# C_v4.net
KiCad netlist of a schematic drawn in EasyEDA Pro
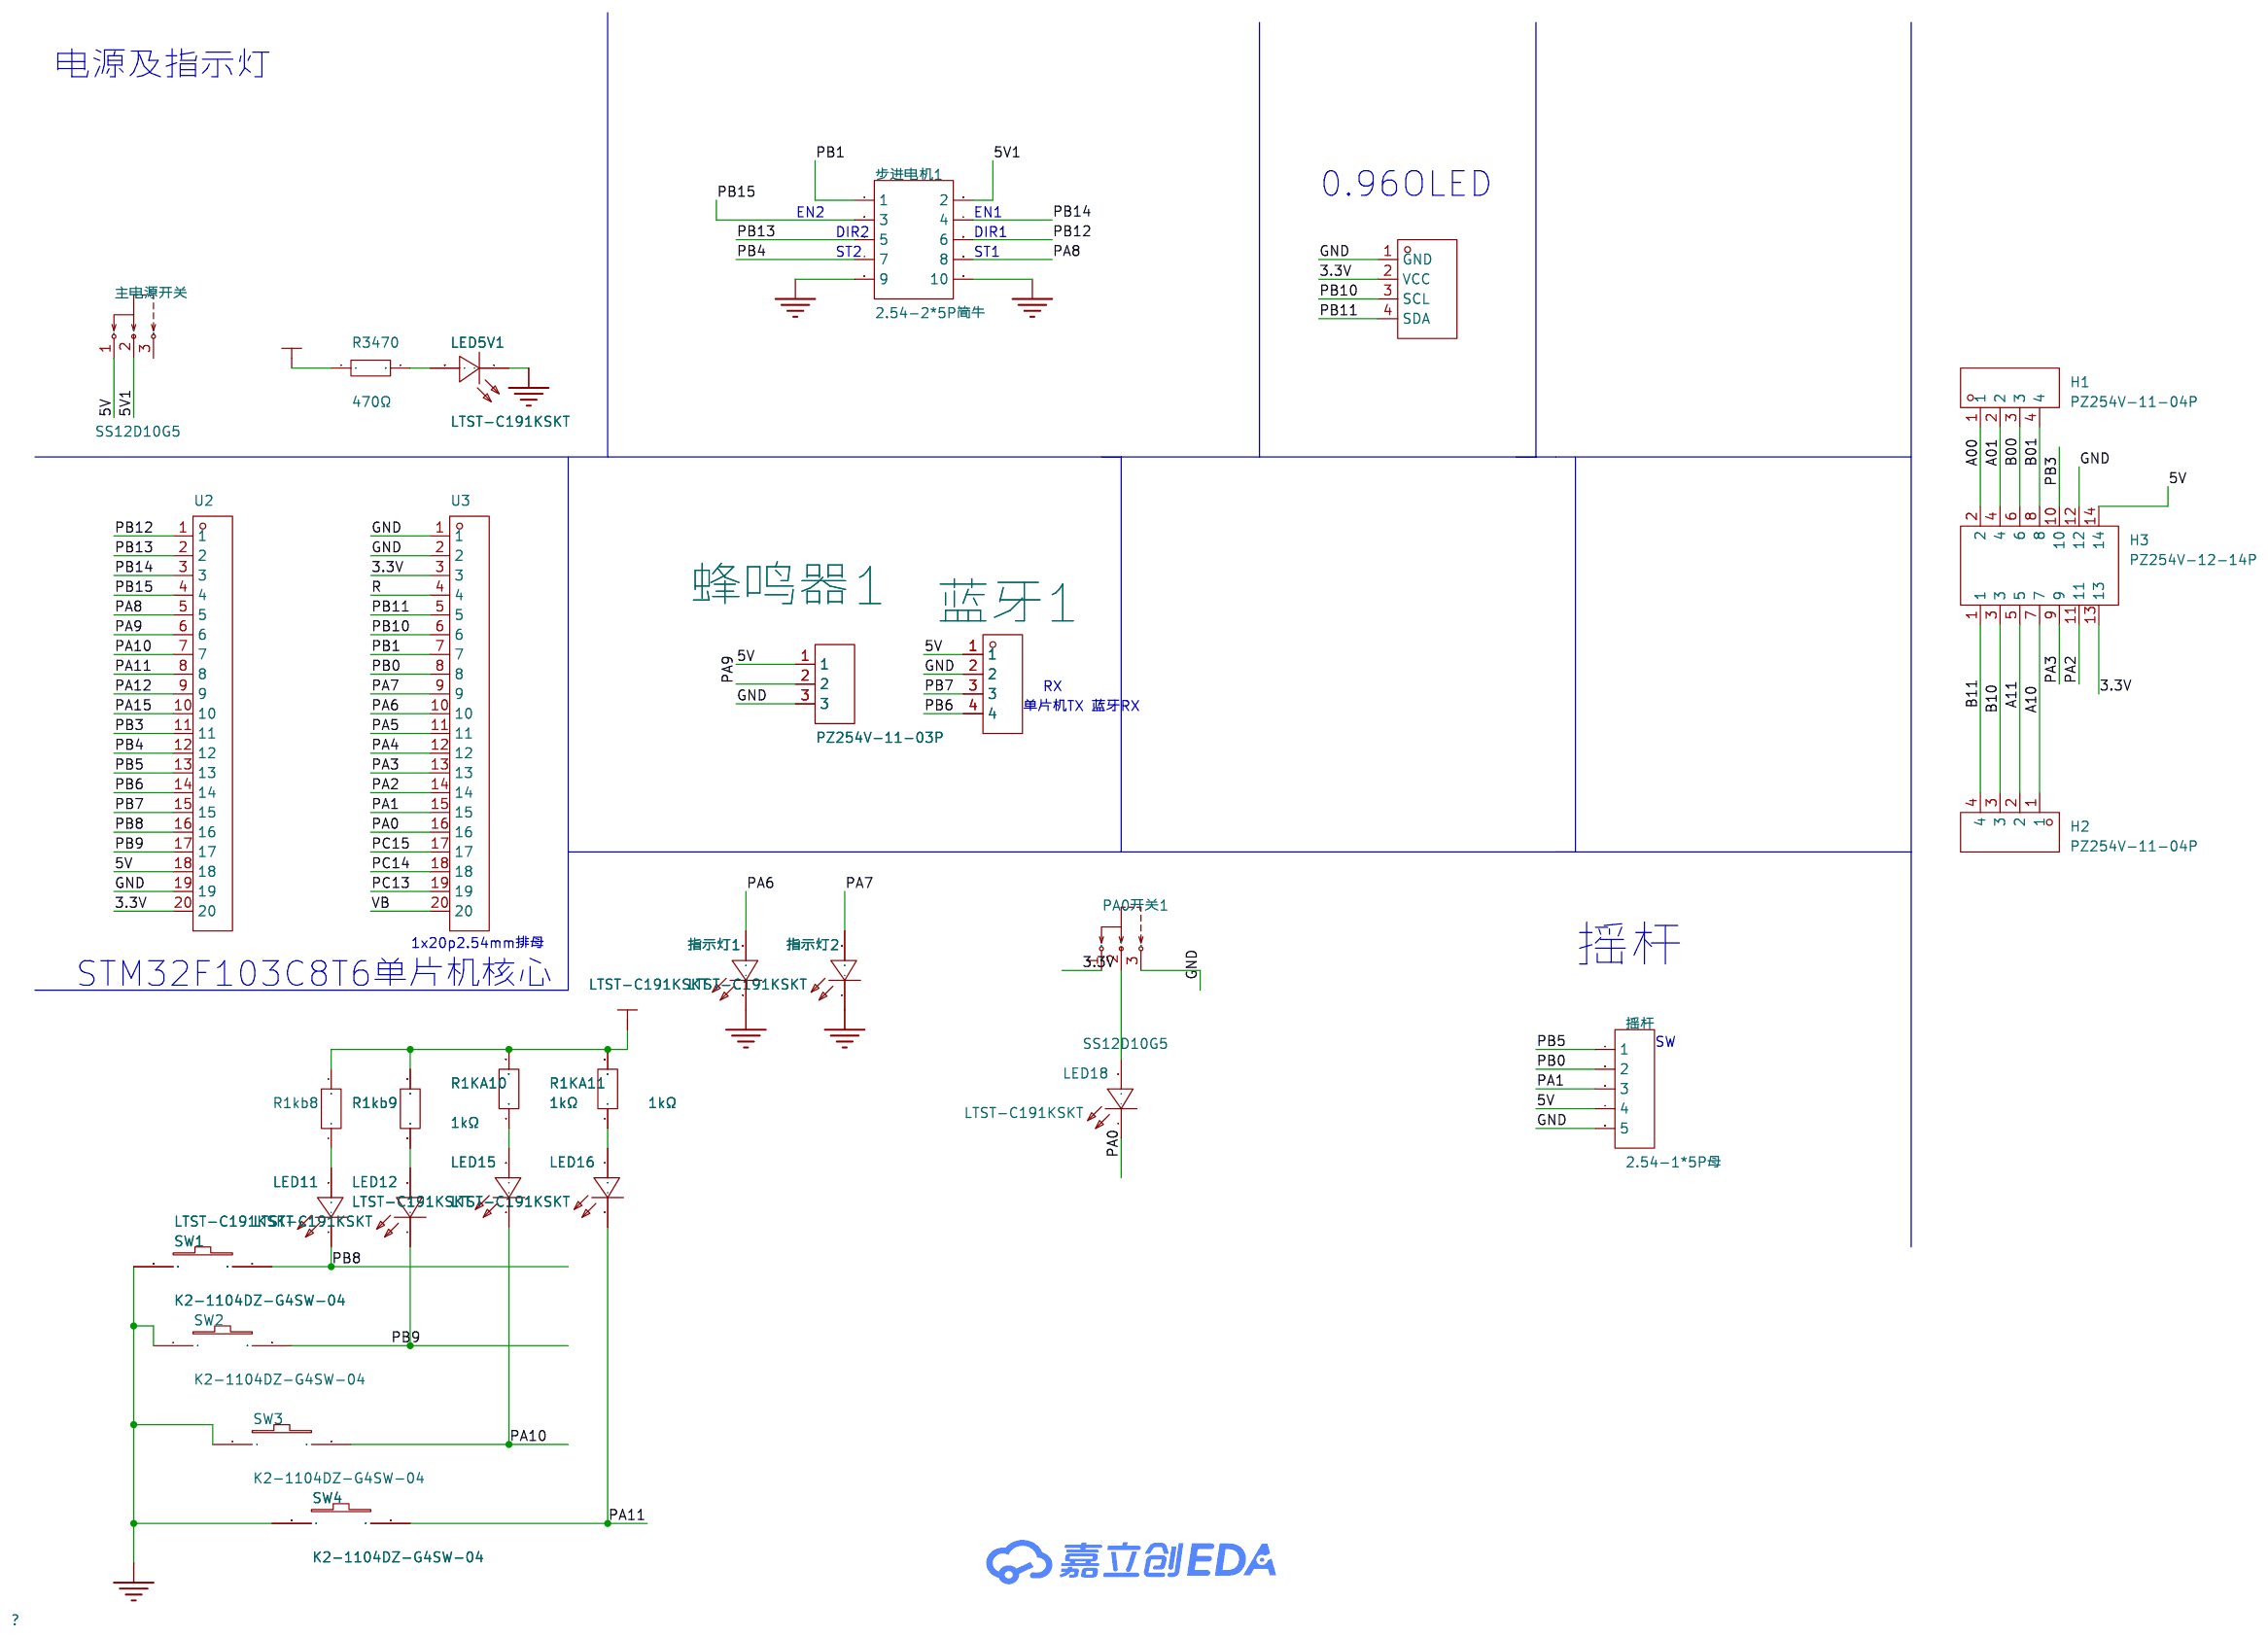
[diagram p0: schematic sheet]

(export (version "E")
  (design (tool "Eeschema 10.0.6"))
  (components
    (comp (ref "H1")
      (value "PZ254V-11-04P")
      (footprint "easyedapro:HDR-TH_4P-P2.54-V-M")
      (fields (field (name "Manufacturer") "XFCN(兴飞)"))
      (libsource (lib "easyedapro") (part "PZ254V-11-04P_C2691448"))
    )
    (comp (ref "H2")
      (value "PZ254V-11-04P")
      (footprint "easyedapro:HDR-TH_4P-P2.54-V-M")
      (fields (field (name "Manufacturer") "XFCN(兴飞)"))
      (libsource (lib "easyedapro") (part "PZ254V-11-04P_C2691448"))
    )
    (comp (ref "H3")
      (value "PZ254V-12-14P")
      (footprint "easyedapro:HDR-TH_14P-P2.54-V-M-R2-C7-S2.54")
      (fields (field (name "Manufacturer") "XFCN(兴飞)"))
      (libsource (lib "easyedapro") (part "PZ254V-12-14P"))
    )
    (comp (ref "LED5V1")
      (value "LTST-C191KSKT")
      (footprint "easyedapro:LED0603-RD-YELLOW")
      (fields (field (name "Manufacturer") "LITEON(光宝)"))
      (libsource (lib "easyedapro") (part "LTST-C191KSKT"))
    )
    (comp (ref "LED11")
      (value "LTST-C191KSKT")
      (footprint "easyedapro:LED0603-RD-YELLOW")
      (fields (field (name "Manufacturer") "LITEON(光宝)"))
      (libsource (lib "easyedapro") (part "LTST-C191KSKT"))
    )
    (comp (ref "LED12")
      (value "LTST-C191KSKT")
      (footprint "easyedapro:LED0603-RD-YELLOW")
      (fields (field (name "Manufacturer") "LITEON(光宝)"))
      (libsource (lib "easyedapro") (part "LTST-C191KSKT"))
    )
    (comp (ref "LED15")
      (value "LTST-C191KSKT")
      (footprint "easyedapro:LED0603-RD-YELLOW")
      (fields (field (name "Manufacturer") "LITEON(光宝)"))
      (libsource (lib "easyedapro") (part "LTST-C191KSKT"))
    )
    (comp (ref "LED16")
      (value "LTST-C191KSKT")
      (footprint "easyedapro:LED0603-RD-YELLOW")
      (fields (field (name "Manufacturer") "LITEON(光宝)"))
      (libsource (lib "easyedapro") (part "LTST-C191KSKT"))
    )
    (comp (ref "LED18")
      (value "LTST-C191KSKT")
      (footprint "easyedapro:LED0603-RD-YELLOW")
      (fields (field (name "Manufacturer") "LITEON(光宝)"))
      (libsource (lib "easyedapro") (part "LTST-C191KSKT"))
    )
    (comp (ref "OLED1")
      (value "HS96L03W2C03")
      (footprint "easyedapro:OLED-TH_L27.8-W27.2-P2.54_C9900033791")
      (description "主控芯片:SSD1315;接口类型:I2C;尺寸(inch):0.96;像素分辨率:128x64;")
      (fields (field (name "Manufacturer") "HS(汉昇)"))
      (libsource (lib "easyedapro") (part "HS96L03W2C03"))
    )
    (comp (ref "PA0开关1")
      (value "SS12D10G5")
      (footprint "easyedapro:SW-TH_SHOU-HAN_SS12D10G4")
      (description "电路结构:单刀双掷;安装方式:直插;额定电流(DC):2A;额定电压(DC):125V;机械寿命:3千次;")
      (fields (field (name "Manufacturer") "SHOU HAN(首韩)"))
      (libsource (lib "easyedapro") (part "SS12D10G5"))
    )
    (comp (ref "R1KA10")
      (value "1kΩ")
      (footprint "easyedapro:R0603")
      (description "电阻类型:厚膜电阻;阻值:1kΩ;精度:±1%;功率:100mW;最大工作电压:75V;")
      (fields (field (name "Manufacturer Part") "FCR0603F1K") (field (name "Manufacturer") "VO(翔胜)"))
      (libsource (lib "easyedapro") (part "FCR0603F1K"))
    )
    (comp (ref "R1KA11")
      (value "1kΩ")
      (footprint "easyedapro:R0603")
      (description "电阻类型:厚膜电阻;阻值:1kΩ;精度:±1%;功率:100mW;最大工作电压:75V;")
      (fields (field (name "Manufacturer Part") "FCR0603F1K") (field (name "Manufacturer") "VO(翔胜)"))
      (libsource (lib "easyedapro") (part "FCR0603F1K"))
    )
    (comp (ref "R1kb8")
      (value "1kΩ")
      (footprint "easyedapro:R0603")
      (description "电阻类型:厚膜电阻;阻值:1kΩ;精度:±1%;功率:100mW;最大工作电压:75V;")
      (fields (field (name "Manufacturer Part") "FCR0603F1K") (field (name "Manufacturer") "VO(翔胜)"))
      (libsource (lib "easyedapro") (part "FCR0603F1K"))
    )
    (comp (ref "R1kb9")
      (value "1kΩ")
      (footprint "easyedapro:R0603")
      (description "电阻类型:厚膜电阻;阻值:1kΩ;精度:±1%;功率:100mW;最大工作电压:75V;")
      (fields (field (name "Manufacturer Part") "FCR0603F1K") (field (name "Manufacturer") "VO(翔胜)"))
      (libsource (lib "easyedapro") (part "FCR0603F1K"))
    )
    (comp (ref "R3470")
      (value "470Ω")
      (footprint "easyedapro:R0603")
      (description "电阻类型:厚膜电阻;阻值:470Ω;精度:±1%;功率:100mW;最大工作电压:75V;温度系数:±100ppm/°C;")
      (fields
        (field (name "Manufacturer Part") "0603WAF4700T5E")
        (field (name "Manufacturer") "UNI-ROYAL(厚声)")
      )
      (libsource (lib "easyedapro") (part "0603WAF4700T5E"))
    )
    (comp (ref "SW1")
      (value "K2-1104DZ-G4SW-04")
      (footprint "easyedapro:KEY-TH_2P-L6.0-W6.0-P5.00")
      (description "作用力:250gf;安装方式:直插;开关长度:6mm;开关宽度:6mm;开关高度:7mm;触点电流:50mA;额定电压(DC):12V;绝缘电阻:100MΩ;机械寿命:10万次;")
      (fields (field (name "Manufacturer") "韩国韩荣"))
      (libsource (lib "easyedapro") (part "K2-1104DZ-G4SW-04"))
    )
    (comp (ref "SW2")
      (value "K2-1104DZ-G4SW-04")
      (footprint "easyedapro:KEY-TH_2P-L6.0-W6.0-P5.00")
      (description "作用力:250gf;安装方式:直插;开关长度:6mm;开关宽度:6mm;开关高度:7mm;触点电流:50mA;额定电压(DC):12V;绝缘电阻:100MΩ;机械寿命:10万次;")
      (fields (field (name "Manufacturer") "韩国韩荣"))
      (libsource (lib "easyedapro") (part "K2-1104DZ-G4SW-04"))
    )
    (comp (ref "SW3")
      (value "K2-1104DZ-G4SW-04")
      (footprint "easyedapro:KEY-TH_2P-L6.0-W6.0-P5.00")
      (description "作用力:250gf;安装方式:直插;开关长度:6mm;开关宽度:6mm;开关高度:7mm;触点电流:50mA;额定电压(DC):12V;绝缘电阻:100MΩ;机械寿命:10万次;")
      (fields (field (name "Manufacturer") "韩国韩荣"))
      (libsource (lib "easyedapro") (part "K2-1104DZ-G4SW-04"))
    )
    (comp (ref "SW4")
      (value "K2-1104DZ-G4SW-04")
      (footprint "easyedapro:KEY-TH_2P-L6.0-W6.0-P5.00")
      (description "作用力:250gf;安装方式:直插;开关长度:6mm;开关宽度:6mm;开关高度:7mm;触点电流:50mA;额定电压(DC):12V;绝缘电阻:100MΩ;机械寿命:10万次;")
      (fields (field (name "Manufacturer") "韩国韩荣"))
      (libsource (lib "easyedapro") (part "K2-1104DZ-G4SW-04"))
    )
    (comp (ref "U2")
      (value "KH-2FH-1X20P-H4.3")
      (footprint "easyedapro:HDR-TH_20P-P2.00-V-F-A")
      (fields (field (name "Manufacturer") "kinghelm(金航标)"))
      (libsource (lib "easyedapro") (part "KH-2FH-1X20P-H4.3"))
    )
    (comp (ref "U3")
      (value "KH-2FH-1X20P-H4.3")
      (footprint "easyedapro:HDR-TH_20P-P2.00-V-F-A")
      (fields (field (name "Manufacturer") "kinghelm(金航标)"))
      (libsource (lib "easyedapro") (part "KH-2FH-1X20P-H4.3"))
    )
    (comp (ref "主电源开关")
      (value "SS12D10G5")
      (footprint "easyedapro:SW-TH_SHOU-HAN_SS12D10G4")
      (description "电路结构:单刀双掷;安装方式:直插;额定电流(DC):2A;额定电压(DC):125V;机械寿命:3千次;")
      (fields (field (name "Manufacturer") "SHOU HAN(首韩)"))
      (libsource (lib "easyedapro") (part "SS12D10G5"))
    )
    (comp (ref "指示灯1")
      (value "LTST-C191KSKT")
      (footprint "easyedapro:LED0603-RD-YELLOW")
      (fields (field (name "Manufacturer") "LITEON(光宝)"))
      (libsource (lib "easyedapro") (part "LTST-C191KSKT"))
    )
    (comp (ref "指示灯2")
      (value "LTST-C191KSKT")
      (footprint "easyedapro:LED0603-RD-YELLOW")
      (fields (field (name "Manufacturer") "LITEON(光宝)"))
      (libsource (lib "easyedapro") (part "LTST-C191KSKT"))
    )
    (comp (ref "摇杆")
      (value "2.54-1*5P母")
      (footprint "easyedapro:HDR-TH_5P-P2.54-V-F")
      (description "插孔结构:1x5P;间距:2.54mm;行距:-;安装类型:直插;排数:单排;总孔位数:5P;塑高:-;触头材质:-;触头镀层:-;")
      (fields (field (name "Manufacturer") "BOOMELE(博穆精密)"))
      (libsource (lib "easyedapro") (part "Header-Female-2.54_1x5"))
    )
    (comp (ref "步进电机1")
      (value "2.54-2*5P简牛")
      (footprint "easyedapro:IDC-TH_10P-P2.54_C5665")
      (description "连接器类型:简牛座;间距:2.54mm;结构:2x5P;封装形式:直插;行距:2.54mm;排数:2;每排PIN数:5;触头材质:-;触头镀层:-;")
      (fields (field (name "Manufacturer") "BOOMELE(博穆精密)"))
      (libsource (lib "easyedapro") (part "HDR-IDC-2.54-2X5P"))
    )
    (comp (ref "蓝牙1")
      (value "2.54-1*4P母")
      (footprint "easyedapro:HDR-TH_4P-P2.54-V-F")
      (fields (field (name "Manufacturer") "BOOMELE(博穆精密)"))
      (libsource (lib "easyedapro") (part "2.54-1*4P母"))
    )
    (comp (ref "蜂鸣器1")
      (value "PZ254V-11-03P")
      (footprint "easyedapro:HDR-TH_3P-P2.54-V-M")
      (fields (field (name "Manufacturer") "XFCN(兴飞)"))
      (libsource (lib "easyedapro") (part "PZ254V-11-03P_C2937625"))
    )
  )
  (nets
    (net (code "1") (name "/5V1") (class "Default")
      (node (ref "主电源开关") (pin "2") (pinfunction "2_2") (pintype "unspecified"))
      (node (ref "步进电机1") (pin "2") (pinfunction "2_2") (pintype "unspecified"))
    )
    (net (code "2") (name "/A00") (class "Default")
      (node (ref "H1") (pin "1") (pinfunction "1_1") (pintype "unspecified"))
      (node (ref "H3") (pin "2") (pinfunction "2_2") (pintype "unspecified"))
    )
    (net (code "3") (name "/A01") (class "Default")
      (node (ref "H1") (pin "2") (pinfunction "2_2") (pintype "unspecified"))
      (node (ref "H3") (pin "4") (pinfunction "4_4") (pintype "unspecified"))
    )
    (net (code "4") (name "/A10") (class "Default")
      (node (ref "H2") (pin "1") (pinfunction "1_1") (pintype "unspecified"))
      (node (ref "H3") (pin "7") (pinfunction "7_7") (pintype "unspecified"))
    )
    (net (code "5") (name "/A11") (class "Default")
      (node (ref "H2") (pin "2") (pinfunction "2_2") (pintype "unspecified"))
      (node (ref "H3") (pin "5") (pinfunction "5_5") (pintype "unspecified"))
    )
    (net (code "6") (name "/B00") (class "Default")
      (node (ref "H1") (pin "3") (pinfunction "3_3") (pintype "unspecified"))
      (node (ref "H3") (pin "6") (pinfunction "6_6") (pintype "unspecified"))
    )
    (net (code "7") (name "/B01") (class "Default")
      (node (ref "H1") (pin "4") (pinfunction "4_4") (pintype "unspecified"))
      (node (ref "H3") (pin "8") (pinfunction "8_8") (pintype "unspecified"))
    )
    (net (code "8") (name "/B10") (class "Default")
      (node (ref "H2") (pin "3") (pinfunction "3_3") (pintype "unspecified"))
      (node (ref "H3") (pin "3") (pinfunction "3_3") (pintype "unspecified"))
    )
    (net (code "9") (name "/B11") (class "Default")
      (node (ref "H2") (pin "4") (pinfunction "4_4") (pintype "unspecified"))
      (node (ref "H3") (pin "1") (pinfunction "1_1") (pintype "unspecified"))
    )
    (net (code "10") (name "/PA0") (class "Default")
      (node (ref "LED18") (pin "1") (pinfunction "-_1") (pintype "unspecified"))
      (node (ref "U3") (pin "16") (pinfunction "16_16") (pintype "unspecified"))
    )
    (net (code "11") (name "/PA1") (class "Default")
      (node (ref "U3") (pin "15") (pinfunction "15_15") (pintype "unspecified"))
      (node (ref "摇杆") (pin "3") (pinfunction "3_3") (pintype "input"))
    )
    (net (code "12") (name "/PA2") (class "Default")
      (node (ref "H3") (pin "11") (pinfunction "11_11") (pintype "unspecified"))
      (node (ref "U3") (pin "14") (pinfunction "14_14") (pintype "unspecified"))
    )
    (net (code "13") (name "/PA3") (class "Default")
      (node (ref "H3") (pin "9") (pinfunction "9_9") (pintype "unspecified"))
      (node (ref "U3") (pin "13") (pinfunction "13_13") (pintype "unspecified"))
    )
    (net (code "14") (name "/PA4") (class "Default")
      (node (ref "U3") (pin "12") (pinfunction "12_12") (pintype "unspecified"))
    )
    (net (code "15") (name "/PA5") (class "Default")
      (node (ref "U3") (pin "11") (pinfunction "11_11") (pintype "unspecified"))
    )
    (net (code "16") (name "/PA6") (class "Default")
      (node (ref "U3") (pin "10") (pinfunction "10_10") (pintype "unspecified"))
      (node (ref "指示灯1") (pin "2") (pinfunction "+_2") (pintype "unspecified"))
    )
    (net (code "17") (name "/PA7") (class "Default")
      (node (ref "U3") (pin "9") (pinfunction "9_9") (pintype "unspecified"))
      (node (ref "指示灯2") (pin "2") (pinfunction "+_2") (pintype "unspecified"))
    )
    (net (code "18") (name "/PA8") (class "Default")
      (node (ref "U2") (pin "5") (pinfunction "5_5") (pintype "unspecified"))
      (node (ref "步进电机1") (pin "8") (pinfunction "8_8") (pintype "unspecified"))
    )
    (net (code "19") (name "/PA9") (class "Default")
      (node (ref "U2") (pin "6") (pinfunction "6_6") (pintype "unspecified"))
      (node (ref "蜂鸣器1") (pin "2") (pinfunction "2_2") (pintype "unspecified"))
    )
    (net (code "20") (name "/PA10") (class "Default")
      (node (ref "LED15") (pin "1") (pinfunction "-_1") (pintype "unspecified"))
      (node (ref "SW3") (pin "2") (pinfunction "2_2") (pintype "input"))
      (node (ref "U2") (pin "7") (pinfunction "7_7") (pintype "unspecified"))
    )
    (net (code "21") (name "/PA11") (class "Default")
      (node (ref "LED16") (pin "1") (pinfunction "-_1") (pintype "unspecified"))
      (node (ref "SW4") (pin "2") (pinfunction "2_2") (pintype "input"))
      (node (ref "U2") (pin "8") (pinfunction "8_8") (pintype "unspecified"))
    )
    (net (code "22") (name "/PA12") (class "Default")
      (node (ref "U2") (pin "9") (pinfunction "9_9") (pintype "unspecified"))
    )
    (net (code "23") (name "/PA15") (class "Default")
      (node (ref "U2") (pin "10") (pinfunction "10_10") (pintype "unspecified"))
    )
    (net (code "24") (name "/PB0") (class "Default")
      (node (ref "U3") (pin "8") (pinfunction "8_8") (pintype "unspecified"))
      (node (ref "摇杆") (pin "2") (pinfunction "2_2") (pintype "input"))
    )
    (net (code "25") (name "/PB1") (class "Default")
      (node (ref "U3") (pin "7") (pinfunction "7_7") (pintype "unspecified"))
      (node (ref "步进电机1") (pin "1") (pinfunction "1_1") (pintype "unspecified"))
    )
    (net (code "26") (name "/PB3") (class "Default")
      (node (ref "H3") (pin "10") (pinfunction "10_10") (pintype "unspecified"))
      (node (ref "U2") (pin "11") (pinfunction "11_11") (pintype "unspecified"))
    )
    (net (code "27") (name "/PB4") (class "Default")
      (node (ref "U2") (pin "12") (pinfunction "12_12") (pintype "unspecified"))
      (node (ref "步进电机1") (pin "7") (pinfunction "7_7") (pintype "unspecified"))
    )
    (net (code "28") (name "/PB5") (class "Default")
      (node (ref "U2") (pin "13") (pinfunction "13_13") (pintype "unspecified"))
      (node (ref "摇杆") (pin "1") (pinfunction "1_1") (pintype "input"))
    )
    (net (code "29") (name "/PB6") (class "Default")
      (node (ref "U2") (pin "14") (pinfunction "14_14") (pintype "unspecified"))
      (node (ref "蓝牙1") (pin "4") (pinfunction "4_4") (pintype "unspecified"))
    )
    (net (code "30") (name "/PB7") (class "Default")
      (node (ref "U2") (pin "15") (pinfunction "15_15") (pintype "unspecified"))
      (node (ref "蓝牙1") (pin "3") (pinfunction "3_3") (pintype "unspecified"))
    )
    (net (code "31") (name "/PB8") (class "Default")
      (node (ref "LED11") (pin "1") (pinfunction "-_1") (pintype "unspecified"))
      (node (ref "SW1") (pin "2") (pinfunction "2_2") (pintype "input"))
      (node (ref "U2") (pin "16") (pinfunction "16_16") (pintype "unspecified"))
    )
    (net (code "32") (name "/PB9") (class "Default")
      (node (ref "LED12") (pin "1") (pinfunction "-_1") (pintype "unspecified"))
      (node (ref "SW2") (pin "2") (pinfunction "2_2") (pintype "input"))
      (node (ref "U2") (pin "17") (pinfunction "17_17") (pintype "unspecified"))
    )
    (net (code "33") (name "/PB10") (class "Default")
      (node (ref "OLED1") (pin "3") (pinfunction "SCL_3") (pintype "unspecified"))
      (node (ref "U3") (pin "6") (pinfunction "6_6") (pintype "unspecified"))
    )
    (net (code "34") (name "/PB11") (class "Default")
      (node (ref "OLED1") (pin "4") (pinfunction "SDA_4") (pintype "unspecified"))
      (node (ref "U3") (pin "5") (pinfunction "5_5") (pintype "unspecified"))
    )
    (net (code "35") (name "/PB12") (class "Default")
      (node (ref "U2") (pin "1") (pinfunction "1_1") (pintype "unspecified"))
      (node (ref "步进电机1") (pin "6") (pinfunction "6_6") (pintype "unspecified"))
    )
    (net (code "36") (name "/PB13") (class "Default")
      (node (ref "U2") (pin "2") (pinfunction "2_2") (pintype "unspecified"))
      (node (ref "步进电机1") (pin "5") (pinfunction "5_5") (pintype "unspecified"))
    )
    (net (code "37") (name "/PB14") (class "Default")
      (node (ref "U2") (pin "3") (pinfunction "3_3") (pintype "unspecified"))
      (node (ref "步进电机1") (pin "4") (pinfunction "4_4") (pintype "unspecified"))
    )
    (net (code "38") (name "/PB15") (class "Default")
      (node (ref "U2") (pin "4") (pinfunction "4_4") (pintype "unspecified"))
      (node (ref "步进电机1") (pin "3") (pinfunction "3_3") (pintype "unspecified"))
    )
    (net (code "39") (name "/PC13") (class "Default")
      (node (ref "U3") (pin "19") (pinfunction "19_19") (pintype "unspecified"))
    )
    (net (code "40") (name "/PC14") (class "Default")
      (node (ref "U3") (pin "18") (pinfunction "18_18") (pintype "unspecified"))
    )
    (net (code "41") (name "/PC15") (class "Default")
      (node (ref "U3") (pin "17") (pinfunction "17_17") (pintype "unspecified"))
    )
    (net (code "42") (name "/R") (class "Default")
      (node (ref "U3") (pin "4") (pinfunction "4_4") (pintype "unspecified"))
    )
    (net (code "43") (name "/VB") (class "Default")
      (node (ref "U3") (pin "20") (pinfunction "20_20") (pintype "unspecified"))
    )
    (net (code "44") (name "3.3V") (class "Default")
      (node (ref "H3") (pin "13") (pinfunction "13_13") (pintype "unspecified"))
      (node (ref "OLED1") (pin "2") (pinfunction "VCC_2") (pintype "unspecified"))
      (node (ref "PA0开关1") (pin "1") (pinfunction "1_1") (pintype "unspecified"))
      (node (ref "R1KA10") (pin "2") (pinfunction "2_2") (pintype "unspecified"))
      (node (ref "R1KA11") (pin "2") (pinfunction "2_2") (pintype "unspecified"))
      (node (ref "R1kb8") (pin "2") (pinfunction "2_2") (pintype "unspecified"))
      (node (ref "R1kb9") (pin "2") (pinfunction "2_2") (pintype "unspecified"))
      (node (ref "U2") (pin "20") (pinfunction "20_20") (pintype "unspecified"))
      (node (ref "U3") (pin "3") (pinfunction "3_3") (pintype "unspecified"))
    )
    (net (code "45") (name "5V") (class "Default")
      (node (ref "H3") (pin "14") (pinfunction "14_14") (pintype "unspecified"))
      (node (ref "R3470") (pin "1") (pinfunction "1_1") (pintype "input"))
      (node (ref "U2") (pin "18") (pinfunction "18_18") (pintype "unspecified"))
      (node (ref "主电源开关") (pin "1") (pinfunction "1_1") (pintype "unspecified"))
      (node (ref "摇杆") (pin "4") (pinfunction "4_4") (pintype "input"))
      (node (ref "蓝牙1") (pin "1") (pinfunction "1_1") (pintype "unspecified"))
      (node (ref "蜂鸣器1") (pin "1") (pinfunction "1_1") (pintype "unspecified"))
    )
    (net (code "46") (name "GND") (class "Default")
      (node (ref "H3") (pin "12") (pinfunction "12_12") (pintype "unspecified"))
      (node (ref "LED5V1") (pin "1") (pinfunction "-_1") (pintype "unspecified"))
      (node (ref "OLED1") (pin "1") (pinfunction "GND_1") (pintype "unspecified"))
      (node (ref "PA0开关1") (pin "3") (pinfunction "3_3") (pintype "unspecified"))
      (node (ref "SW1") (pin "1") (pinfunction "1_1") (pintype "input"))
      (node (ref "SW2") (pin "1") (pinfunction "1_1") (pintype "input"))
      (node (ref "SW3") (pin "1") (pinfunction "1_1") (pintype "input"))
      (node (ref "SW4") (pin "1") (pinfunction "1_1") (pintype "input"))
      (node (ref "U2") (pin "19") (pinfunction "19_19") (pintype "unspecified"))
      (node (ref "U3") (pin "1") (pinfunction "1_1") (pintype "unspecified"))
      (node (ref "U3") (pin "2") (pinfunction "2_2") (pintype "unspecified"))
      (node (ref "指示灯1") (pin "1") (pinfunction "-_1") (pintype "unspecified"))
      (node (ref "指示灯2") (pin "1") (pinfunction "-_1") (pintype "unspecified"))
      (node (ref "摇杆") (pin "5") (pinfunction "5_5") (pintype "input"))
      (node (ref "步进电机1") (pin "10") (pinfunction "10_10") (pintype "unspecified"))
      (node (ref "步进电机1") (pin "9") (pinfunction "9_9") (pintype "unspecified"))
      (node (ref "蓝牙1") (pin "2") (pinfunction "2_2") (pintype "unspecified"))
      (node (ref "蜂鸣器1") (pin "3") (pinfunction "3_3") (pintype "unspecified"))
    )
    (net (code "47") (name "Net-(LED5V1-+)") (class "Default")
      (node (ref "LED5V1") (pin "2") (pinfunction "+_2") (pintype "unspecified"))
      (node (ref "R3470") (pin "2") (pinfunction "2_2") (pintype "input"))
    )
    (net (code "48") (name "Net-(LED11-+)") (class "Default")
      (node (ref "LED11") (pin "2") (pinfunction "+_2") (pintype "unspecified"))
      (node (ref "R1kb8") (pin "1") (pinfunction "1_1") (pintype "unspecified"))
    )
    (net (code "49") (name "Net-(LED12-+)") (class "Default")
      (node (ref "LED12") (pin "2") (pinfunction "+_2") (pintype "unspecified"))
      (node (ref "R1kb9") (pin "1") (pinfunction "1_1") (pintype "unspecified"))
    )
    (net (code "50") (name "Net-(LED15-+)") (class "Default")
      (node (ref "LED15") (pin "2") (pinfunction "+_2") (pintype "unspecified"))
      (node (ref "R1KA10") (pin "1") (pinfunction "1_1") (pintype "unspecified"))
    )
    (net (code "51") (name "Net-(LED16-+)") (class "Default")
      (node (ref "LED16") (pin "2") (pinfunction "+_2") (pintype "unspecified"))
      (node (ref "R1KA11") (pin "1") (pinfunction "1_1") (pintype "unspecified"))
    )
    (net (code "52") (name "Net-(LED18-+)") (class "Default")
      (node (ref "LED18") (pin "2") (pinfunction "+_2") (pintype "unspecified"))
      (node (ref "PA0开关1") (pin "2") (pinfunction "2_2") (pintype "unspecified"))
    )
    (net (code "53") (name "unconnected-(主电源开关-Pad3)") (class "Default")
      (node (ref "主电源开关") (pin "3") (pinfunction "3_3") (pintype "unspecified"))
    )
  )
)
